# ProPrj_VEX_Competition_Switch_Solo_2025-.net
KiCad netlist of a schematic drawn in EasyEDA Pro
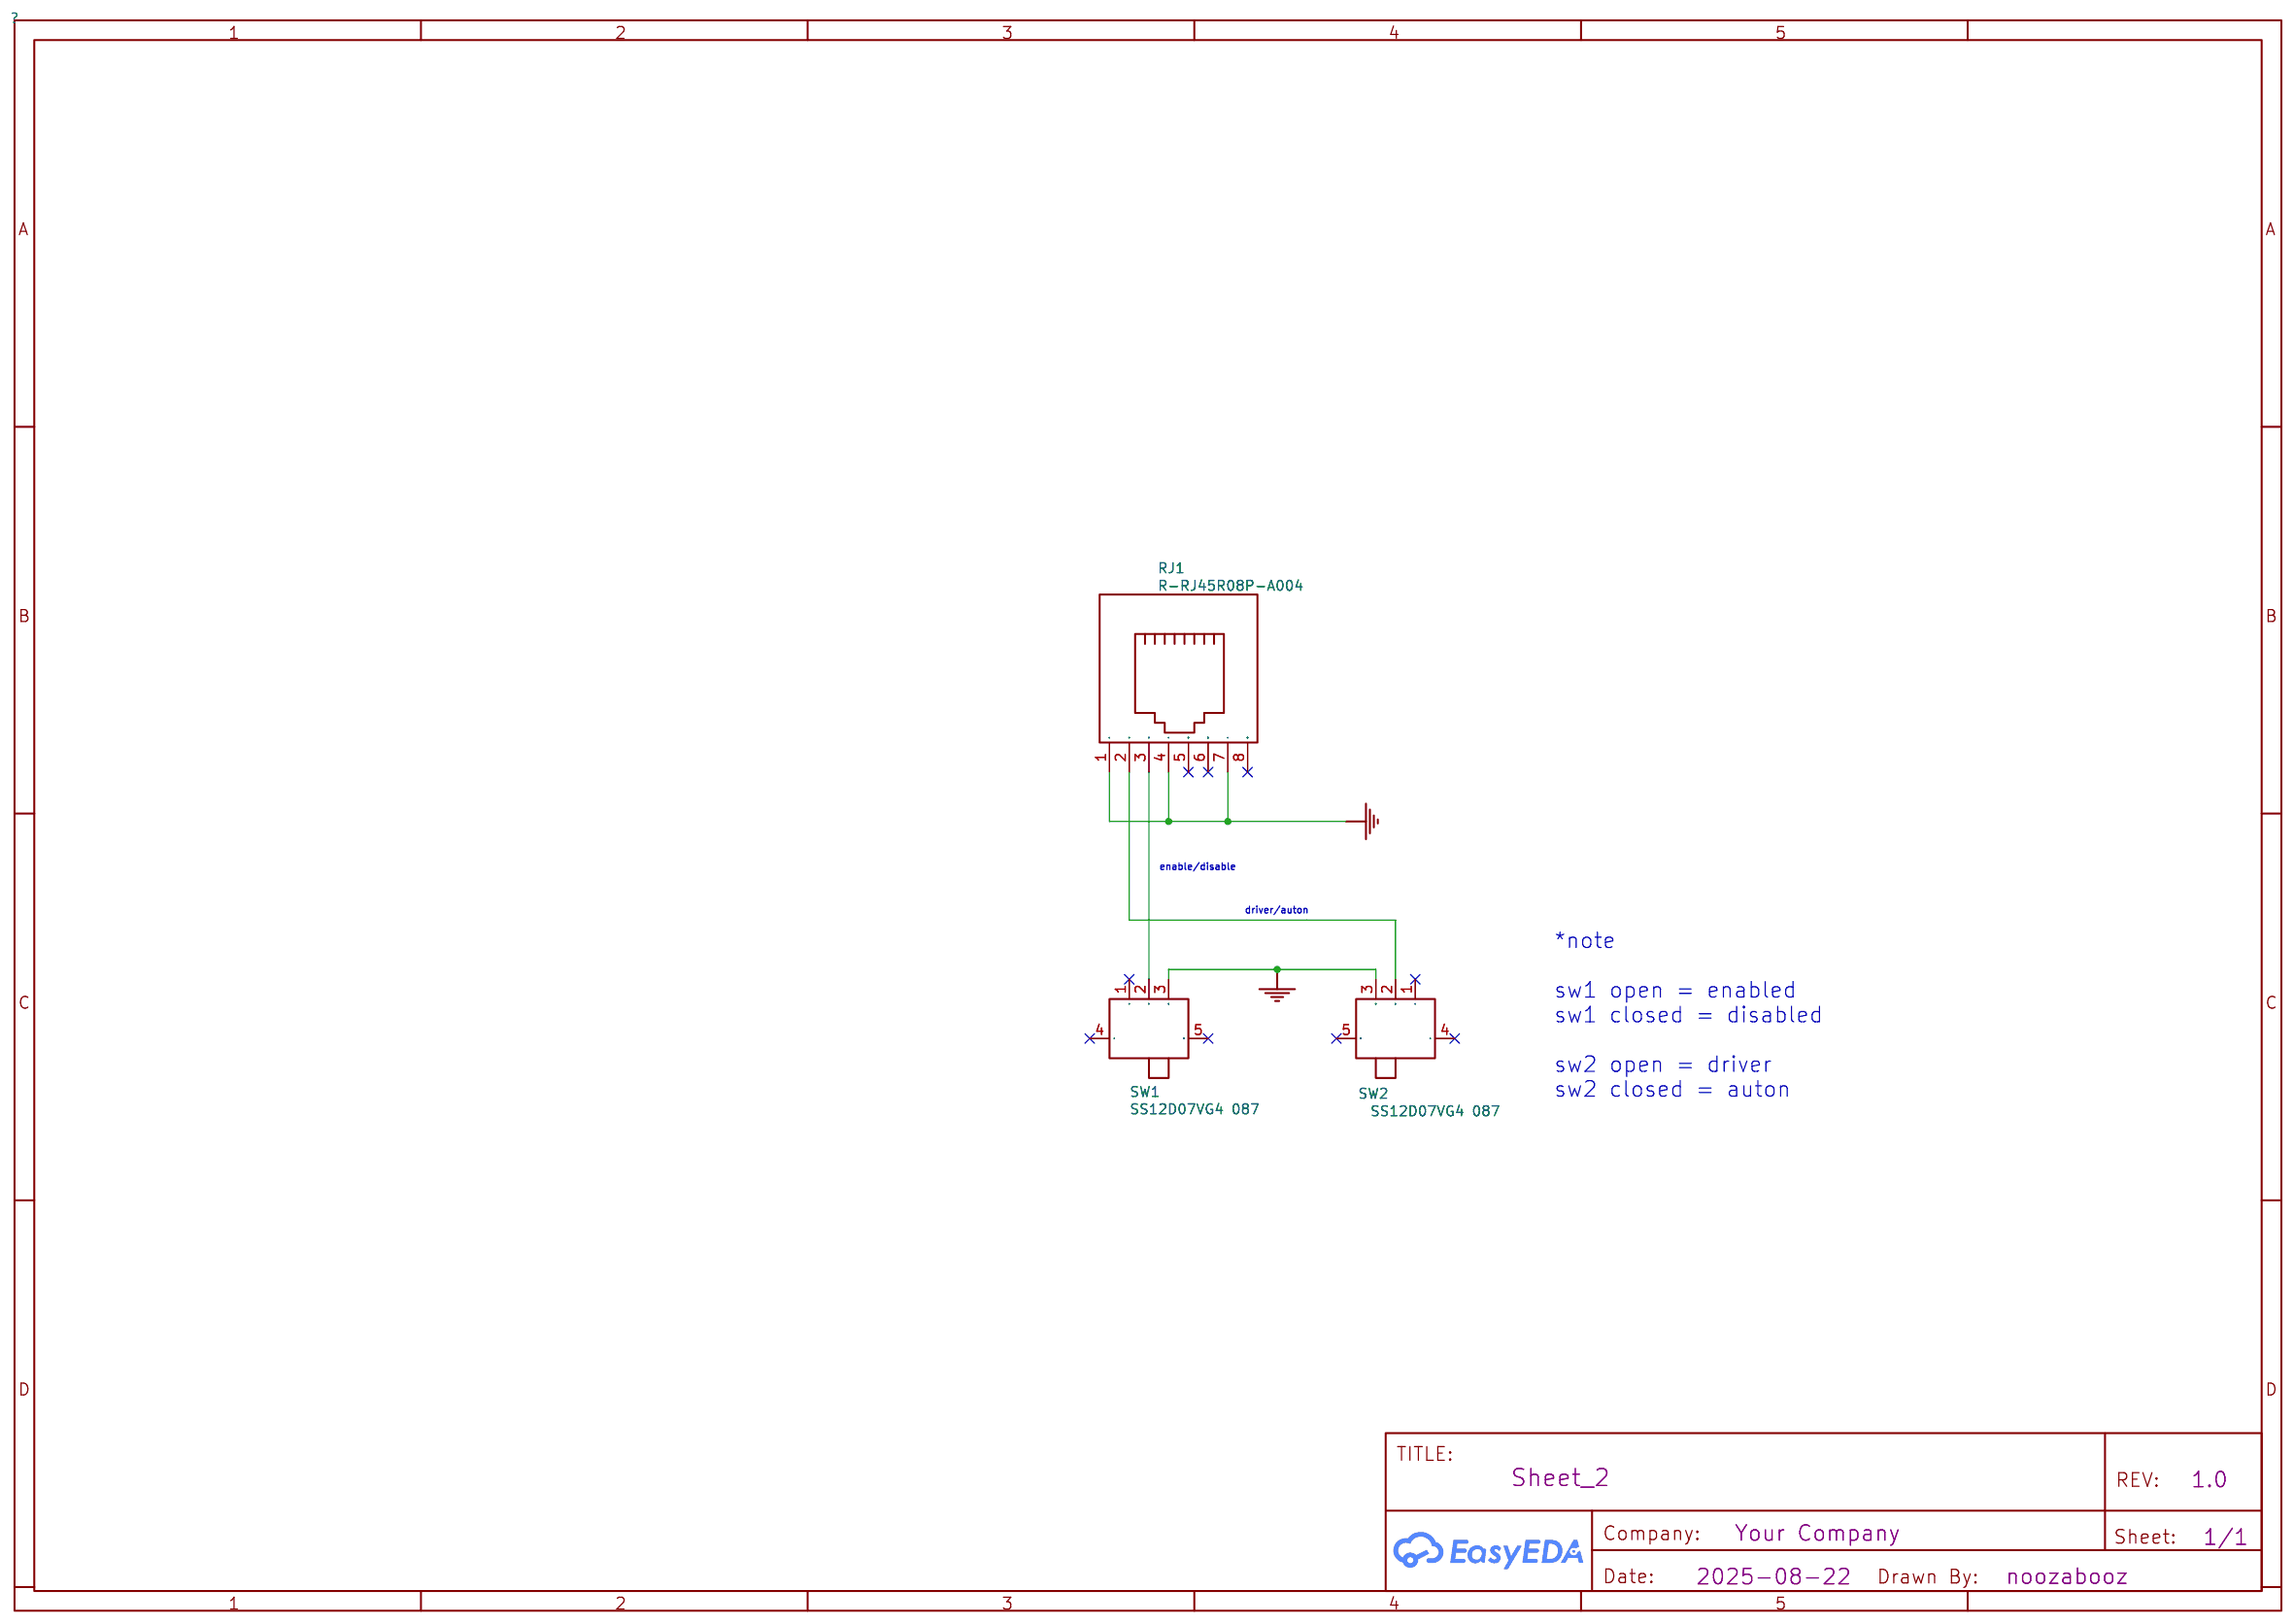
[diagram p0: schematic sheet]

(export (version "E")
  (design (tool "Eeschema 10.0.6"))
  (components
    (comp (ref "RJ1")
      (value "R-RJ45R08P-A004")
      (footprint "easyedapro:RJ45-TH_R-RJ45R08P-A004")
      (fields (field (name "Manufacturer") "Ckmtw(灿科盟)") (field (name "Contributor") "LCSC"))
      (libsource (lib "easyedapro") (part "R-RJ45R08P-A004"))
    )
    (comp (ref "SW1")
      (value "SS12D07VG4 087")
      (footprint "easyedapro:SW-TH_SS12D07VG4")
      (fields (field (name "Manufacturer") "SHOU HAN(首韩)") (field (name "Contributor") "LCSC"))
      (libsource (lib "") (part "SS12D07VG4 087_1"))
    )
    (comp (ref "SW2")
      (value "SS12D07VG4 087")
      (footprint "easyedapro:SW-TH_SS12D07VG4")
      (fields (field (name "Manufacturer") "SHOU HAN(首韩)") (field (name "Contributor") "LCSC"))
      (libsource (lib "easyedapro") (part "SS12D07VG4 087"))
    )
  )
  (nets
    (net (code "1") (name "GND") (class "Default")
      (node (ref "RJ1") (pin "1") (pinfunction "1_1") (pintype "unspecified"))
      (node (ref "RJ1") (pin "4") (pinfunction "4_4") (pintype "unspecified"))
      (node (ref "RJ1") (pin "7") (pinfunction "7_7") (pintype "unspecified"))
      (node (ref "SW1") (pin "3") (pinfunction "3_3") (pintype "unspecified"))
      (node (ref "SW2") (pin "3") (pinfunction "3_3") (pintype "unspecified"))
    )
    (net (code "2") (name "Net-(RJ1-Pad2)") (class "Default")
      (node (ref "RJ1") (pin "2") (pinfunction "2_2") (pintype "unspecified"))
      (node (ref "SW2") (pin "2") (pinfunction "2_2") (pintype "unspecified"))
    )
    (net (code "3") (name "Net-(RJ1-Pad3)") (class "Default")
      (node (ref "RJ1") (pin "3") (pinfunction "3_3") (pintype "unspecified"))
      (node (ref "SW1") (pin "2") (pinfunction "2_2") (pintype "unspecified"))
    )
    (net (code "4") (name "unconnected-(RJ1-Pad5)") (class "Default")
      (node (ref "RJ1") (pin "5") (pinfunction "5_5") (pintype "unspecified+no_connect"))
    )
    (net (code "5") (name "unconnected-(RJ1-Pad6)") (class "Default")
      (node (ref "RJ1") (pin "6") (pinfunction "6_6") (pintype "unspecified+no_connect"))
    )
    (net (code "6") (name "unconnected-(RJ1-Pad8)") (class "Default")
      (node (ref "RJ1") (pin "8") (pinfunction "8_8") (pintype "unspecified+no_connect"))
    )
    (net (code "7") (name "unconnected-(SW1-Pad1)") (class "Default")
      (node (ref "SW1") (pin "1") (pinfunction "1_1") (pintype "unspecified+no_connect"))
    )
    (net (code "8") (name "unconnected-(SW1-Pad4)") (class "Default")
      (node (ref "SW1") (pin "4") (pinfunction "4_4") (pintype "unspecified+no_connect"))
    )
    (net (code "9") (name "unconnected-(SW1-Pad5)") (class "Default")
      (node (ref "SW1") (pin "5") (pinfunction "5_5") (pintype "unspecified+no_connect"))
    )
    (net (code "10") (name "unconnected-(SW2-Pad1)") (class "Default")
      (node (ref "SW2") (pin "1") (pinfunction "1_1") (pintype "unspecified+no_connect"))
    )
    (net (code "11") (name "unconnected-(SW2-Pad4)") (class "Default")
      (node (ref "SW2") (pin "4") (pinfunction "4_4") (pintype "unspecified+no_connect"))
    )
    (net (code "12") (name "unconnected-(SW2-Pad5)") (class "Default")
      (node (ref "SW2") (pin "5") (pinfunction "5_5") (pintype "unspecified+no_connect"))
    )
  )
)
